# USB.net
KiCad netlist of a schematic drawn in Altium Designer
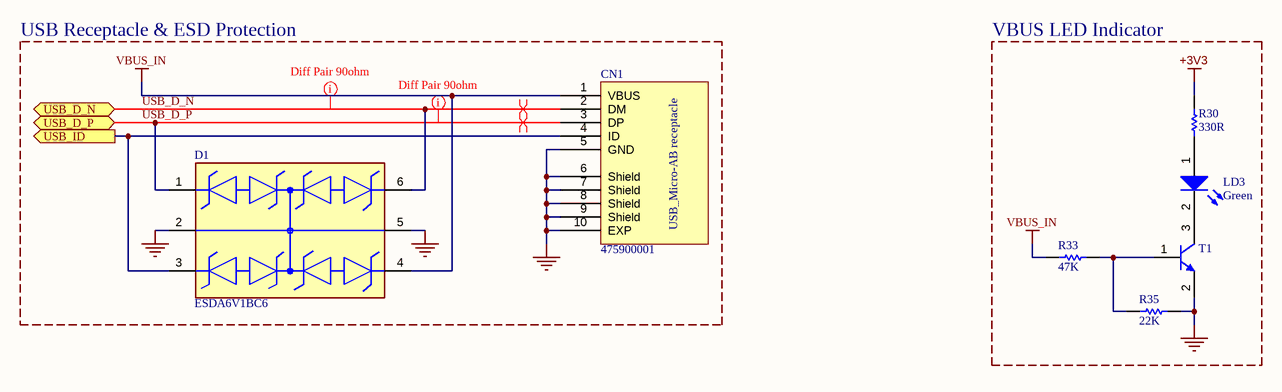
[diagram p0: USB.SchDoc]

(export (version "E")
  (design (tool "Eeschema 10.0.6"))
  (components
    (comp (ref "CN1")
      (value "475900001")
      (footprint "MOLEX_47590001")
      (libsource (lib "mb1045") (part "475900001"))
    )
    (comp (ref "D1")
      (value "ESDA6V1BC6")
      (footprint "FP-SOT23-6L-MFG")
      (description "TVS DIODE 5V SOT23-6")
      (fields
        (field (name "MANUFACTURER") "STMicroelectronics")
        (field (name "OCTOPART") "https://octopart.com/esda6v1bc6-stmicroelectronics-347715")
      )
      (libsource (lib "Altium Content Vault") (part "3fc8afaed3c8ed0e97b36f4d4f9a65f"))
    )
    (comp (ref "LD3")
      (value "Green")
      (footprint "0603D-G")
      (description "Typical RED, GREEN, YELLOW, AMBER GaAs LED")
      (fields (field (name "PUBLISHER") "Altium Limited"))
      (libsource (lib "Miscellaneous Devices") (part "LED2"))
    )
    (comp (ref "R30")
      (value "330R")
      (footprint "0603R")
      (description "Resistor")
      (fields (field (name "PUBLISHER") "Altium Limited"))
      (libsource (lib "Miscellaneous Devices") (part "Res1"))
    )
    (comp (ref "R33")
      (value "47K")
      (footprint "0603R")
      (description "Resistor")
      (fields (field (name "PUBLISHER") "Altium Limited"))
      (libsource (lib "Miscellaneous Devices") (part "res1"))
    )
    (comp (ref "R35")
      (value "22K")
      (footprint "0603R")
      (description "Resistor")
      (fields (field (name "PUBLISHER") "Altium Limited"))
      (libsource (lib "Miscellaneous Devices") (part "res1"))
    )
    (comp (ref "T1")
      (value "MMBTA05LT3G")
      (footprint "SOT-23")
      (description "NPN Bipolar Transistor")
      (fields (field (name "PUBLISHER") "Altium Limited"))
      (libsource (lib "MB1167") (part "NPN"))
    )
  )
  (nets
    (net (code "1") (name "+3V3") (class "Default")
      (node (ref "R30") (pin "2") (pinfunction "2_2") (pintype "passive"))
    )
    (net (code "2") (name "/USB_D_N") (class "Default")
      (node (ref "CN1") (pin "2") (pinfunction "DM_2") (pintype "passive"))
      (node (ref "D1") (pin "6") (pinfunction "6_6") (pintype "passive"))
    )
    (net (code "3") (name "/USB_D_P") (class "Default")
      (node (ref "CN1") (pin "3") (pinfunction "DP_3") (pintype "passive"))
      (node (ref "D1") (pin "1") (pinfunction "1_1") (pintype "passive"))
    )
    (net (code "4") (name "/USB_ID") (class "Default")
      (node (ref "CN1") (pin "4") (pinfunction "ID_4") (pintype "passive"))
      (node (ref "D1") (pin "3") (pinfunction "3_3") (pintype "passive"))
    )
    (net (code "5") (name "GND") (class "Default")
      (node (ref "CN1") (pin "10") (pinfunction "EXP_10") (pintype "passive"))
      (node (ref "CN1") (pin "5") (pinfunction "GND_5") (pintype "passive"))
      (node (ref "CN1") (pin "6") (pinfunction "Shield_6") (pintype "passive"))
      (node (ref "CN1") (pin "7") (pinfunction "Shield_7") (pintype "passive"))
      (node (ref "CN1") (pin "8") (pinfunction "Shield_8") (pintype "passive"))
      (node (ref "CN1") (pin "9") (pinfunction "Shield_9") (pintype "passive"))
      (node (ref "D1") (pin "2") (pinfunction "2_2") (pintype "passive"))
      (node (ref "D1") (pin "5") (pinfunction "5_5") (pintype "passive"))
      (node (ref "R35") (pin "1") (pinfunction "1_1") (pintype "passive"))
      (node (ref "T1") (pin "2") (pinfunction "E_2") (pintype "passive"))
    )
    (net (code "6") (name "Net-(LD3-A)") (class "Default")
      (node (ref "LD3") (pin "1") (pinfunction "A_1") (pintype "passive"))
      (node (ref "R30") (pin "1") (pinfunction "1_1") (pintype "passive"))
    )
    (net (code "7") (name "Net-(LD3-K)") (class "Default")
      (node (ref "LD3") (pin "2") (pinfunction "K_2") (pintype "passive"))
      (node (ref "T1") (pin "3") (pinfunction "C_3") (pintype "passive"))
    )
    (net (code "8") (name "Net-(T1-B)") (class "Default")
      (node (ref "R33") (pin "2") (pinfunction "2_2") (pintype "passive"))
      (node (ref "R35") (pin "2") (pinfunction "2_2") (pintype "passive"))
      (node (ref "T1") (pin "1") (pinfunction "B_1") (pintype "passive"))
    )
    (net (code "9") (name "VBUS_IN") (class "Default")
      (node (ref "CN1") (pin "1") (pinfunction "VBUS_1") (pintype "passive"))
      (node (ref "D1") (pin "4") (pinfunction "4_4") (pintype "passive"))
      (node (ref "R33") (pin "1") (pinfunction "1_1") (pintype "passive"))
    )
  )
)
